# v2_0.net
KiCad netlist of a schematic drawn in Altium Designer
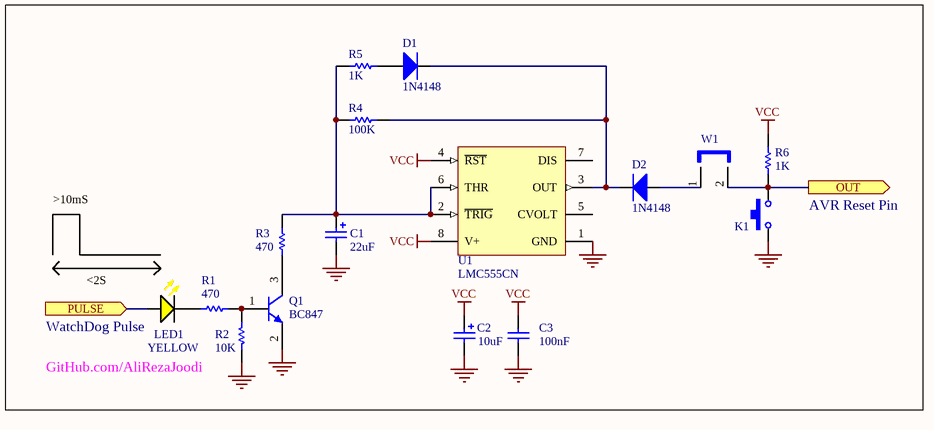
[diagram p0: v2.0.SchDoc]

(export (version "E")
  (design (tool "Eeschema 10.0.6"))
  (components
    (comp (ref "C1")
      (value "22uF")
      (footprint "Cap_B")
      (description "Polarized Capacitor (Radial)")
      (fields (field (name "MANUFACTURER") "Generic Components") (field (name "PUBLISHER") "Altium Limited"))
      (libsource (lib "Miscellaneous Devices") (part "Cap Pol1"))
    )
    (comp (ref "C2")
      (value "10uF")
      (footprint "Cap_B")
      (description "Polarized Capacitor (Radial)")
      (fields (field (name "MANUFACTURER") "Generic Components") (field (name "PUBLISHER") "Altium Limited"))
      (libsource (lib "Miscellaneous Devices") (part "Cap Pol1"))
    )
    (comp (ref "C3")
      (value "100nF")
      (footprint "0805")
      (description "Capacitor")
      (fields (field (name "MANUFACTURER") "Generic Components") (field (name "PUBLISHER") "Altium Limited"))
      (libsource (lib "Miscellaneous Devices") (part "Cap"))
    )
    (comp (ref "D1")
      (value "1N4148")
      (footprint "0805_Diode")
      (description "Default Diode")
      (fields
        (field (name "MANUFACTURER") "Generic Components")
        (field (name "Comment") "Diode")
        (field (name "PUBLISHER") "Altium Limited")
      )
      (libsource (lib "Miscellaneous Devices") (part "Diode"))
    )
    (comp (ref "D2")
      (value "1N4148")
      (footprint "0805_Diode")
      (description "Default Diode")
      (fields
        (field (name "MANUFACTURER") "Generic Components")
        (field (name "Comment") "Diode")
        (field (name "PUBLISHER") "Altium Limited")
      )
      (libsource (lib "Miscellaneous Devices") (part "Diode"))
    )
    (comp (ref "K1")
      (value "Switch_SW-PB")
      (footprint "SWPBT_SPST_6X6X4")
      (description "Switch, SW-PB")
      (fields (field (name "MANUFACTURER") "Generic Components") (field (name "PUBLISHER") "Altium Limited"))
      (libsource (lib "Passive") (part "Switch_SW-PB_2Form"))
    )
    (comp (ref "LED1")
      (value "YELLOW")
      (footprint "LED_THD_3MM_YELLOW_R")
      (description "LED, Yellow")
      (fields (field (name "MANUFACTURER") "Generic Components") (field (name "PUBLISHER") "Altium Limited"))
      (libsource (lib "Display") (part "LED_YELLOW"))
    )
    (comp (ref "Q1")
      (value "BC847")
      (footprint "SOT23-3N")
      (description "Silicon Bipolar Transistor")
      (libsource (lib "my Libraries") (part "BC847"))
    )
    (comp (ref "R1")
      (value "470")
      (footprint "0805")
      (description "Resistor")
      (fields (field (name "PUBLISHER") "Altium Limited"))
      (libsource (lib "Miscellaneous Devices") (part "Res1"))
    )
    (comp (ref "R2")
      (value "10K")
      (footprint "0805")
      (description "Resistor")
      (fields (field (name "Comment") "Res1") (field (name "PUBLISHER") "Altium Limited"))
      (libsource (lib "Miscellaneous Devices") (part "Res1"))
    )
    (comp (ref "R3")
      (value "470")
      (footprint "0805")
      (description "Resistor")
      (fields (field (name "PUBLISHER") "Altium Limited"))
      (libsource (lib "Miscellaneous Devices") (part "Res1"))
    )
    (comp (ref "R4")
      (value "100K")
      (footprint "0805")
      (description "Resistor")
      (fields (field (name "Comment") "Res1") (field (name "PUBLISHER") "Altium Limited"))
      (libsource (lib "Miscellaneous Devices") (part "Res1"))
    )
    (comp (ref "R5")
      (value "1K")
      (footprint "0805")
      (description "Resistor")
      (fields (field (name "Comment") "Res1") (field (name "PUBLISHER") "Altium Limited"))
      (libsource (lib "Miscellaneous Devices") (part "Res1"))
    )
    (comp (ref "R6")
      (value "1K")
      (footprint "0805")
      (description "Resistor")
      (fields (field (name "MANUFACTURER") "Generic Components") (field (name "PUBLISHER") "Altium Limited"))
      (libsource (lib "Miscellaneous Devices") (part "Res1"))
    )
    (comp (ref "U1")
      (value "LMC555CN")
      (footprint "SOP127P636-8N")
      (description "CMOS Timer, 8-pin MDIP")
      (fields
        (field (name "MANUFACTURER") "National Semiconductor")
        (field (name "PUBLISHER") "Altium Limited")
      )
      (libsource (lib "NSC Analog") (part "LMC555CN"))
    )
    (comp (ref "W1")
      (value "Jumper 2pin")
      (footprint "HDR1X2")
      (description "Jumper Wire")
      (fields (field (name "MANUFACTURER") "Generic Components") (field (name "PUBLISHER") "Altium Limited"))
      (libsource (lib "my Libraries") (part "Jumper 2pin"))
    )
  )
  (nets
    (net (code "1") (name "/OUT") (class "Default")
      (node (ref "K1") (pin "2") (pinfunction "2_2") (pintype "passive"))
      (node (ref "R6") (pin "2") (pinfunction "2_2") (pintype "passive"))
      (node (ref "W1") (pin "2") (pinfunction "2_2") (pintype "passive"))
    )
    (net (code "2") (name "/PULSE") (class "Default")
      (node (ref "LED1") (pin "1") (pinfunction "A_1") (pintype "passive"))
    )
    (net (code "3") (name "GND") (class "Default")
      (node (ref "C1") (pin "2") (pinfunction "2_2") (pintype "passive"))
      (node (ref "C2") (pin "2") (pinfunction "2_2") (pintype "passive"))
      (node (ref "C3") (pin "1") (pinfunction "1_1") (pintype "passive"))
      (node (ref "K1") (pin "1") (pinfunction "1_1") (pintype "passive"))
      (node (ref "Q1") (pin "2") (pinfunction "E_2") (pintype "passive"))
      (node (ref "R2") (pin "2") (pinfunction "2_2") (pintype "passive"))
      (node (ref "U1") (pin "1") (pinfunction "GND_1") (pintype "power_in"))
    )
    (net (code "4") (name "Net-(D1-A)") (class "Default")
      (node (ref "D1") (pin "1") (pinfunction "A_1") (pintype "passive"))
      (node (ref "R5") (pin "2") (pinfunction "2_2") (pintype "passive"))
    )
    (net (code "5") (name "Net-(D1-K)") (class "Default")
      (node (ref "D1") (pin "2") (pinfunction "K_2") (pintype "passive"))
      (node (ref "D2") (pin "2") (pinfunction "K_2") (pintype "passive"))
      (node (ref "R4") (pin "1") (pinfunction "1_1") (pintype "passive"))
      (node (ref "U1") (pin "3") (pinfunction "OUT_3") (pintype "output"))
    )
    (net (code "6") (name "Net-(D2-A)") (class "Default")
      (node (ref "D2") (pin "1") (pinfunction "A_1") (pintype "passive"))
      (node (ref "W1") (pin "1") (pinfunction "1_1") (pintype "passive"))
    )
    (net (code "7") (name "Net-(LED1-K)") (class "Default")
      (node (ref "LED1") (pin "2") (pinfunction "K_2") (pintype "passive"))
      (node (ref "R1") (pin "1") (pinfunction "1_1") (pintype "passive"))
    )
    (net (code "8") (name "Net-(Q1-B)") (class "Default")
      (node (ref "Q1") (pin "1") (pinfunction "B_1") (pintype "passive"))
      (node (ref "R1") (pin "2") (pinfunction "2_2") (pintype "passive"))
      (node (ref "R2") (pin "1") (pinfunction "1_1") (pintype "passive"))
    )
    (net (code "9") (name "Net-(Q1-C)") (class "Default")
      (node (ref "Q1") (pin "3") (pinfunction "C_3") (pintype "passive"))
      (node (ref "R3") (pin "1") (pinfunction "1_1") (pintype "passive"))
    )
    (net (code "10") (name "Net-(U1-THR)") (class "Default")
      (node (ref "C1") (pin "1") (pinfunction "1_1") (pintype "passive"))
      (node (ref "R3") (pin "2") (pinfunction "2_2") (pintype "passive"))
      (node (ref "R4") (pin "2") (pinfunction "2_2") (pintype "passive"))
      (node (ref "R5") (pin "1") (pinfunction "1_1") (pintype "passive"))
      (node (ref "U1") (pin "2") (pinfunction "~{TRIG}_2") (pintype "input"))
      (node (ref "U1") (pin "6") (pinfunction "THR_6") (pintype "input"))
    )
    (net (code "11") (name "VCC") (class "Default")
      (node (ref "C2") (pin "1") (pinfunction "1_1") (pintype "passive"))
      (node (ref "C3") (pin "2") (pinfunction "2_2") (pintype "passive"))
      (node (ref "R6") (pin "1") (pinfunction "1_1") (pintype "passive"))
      (node (ref "U1") (pin "4") (pinfunction "~{RST}_4") (pintype "input"))
      (node (ref "U1") (pin "8") (pinfunction "V+_8") (pintype "power_in"))
    )
    (net (code "12") (name "unconnected-(U1-CVOLT-Pad5)") (class "Default")
      (node (ref "U1") (pin "5") (pinfunction "CVOLT_5") (pintype "passive"))
    )
    (net (code "13") (name "unconnected-(U1-DIS-Pad7)") (class "Default")
      (node (ref "U1") (pin "7") (pinfunction "DIS_7") (pintype "open_collector"))
    )
  )
)
